# USB.net
KiCad netlist of a schematic drawn in Altium Designer
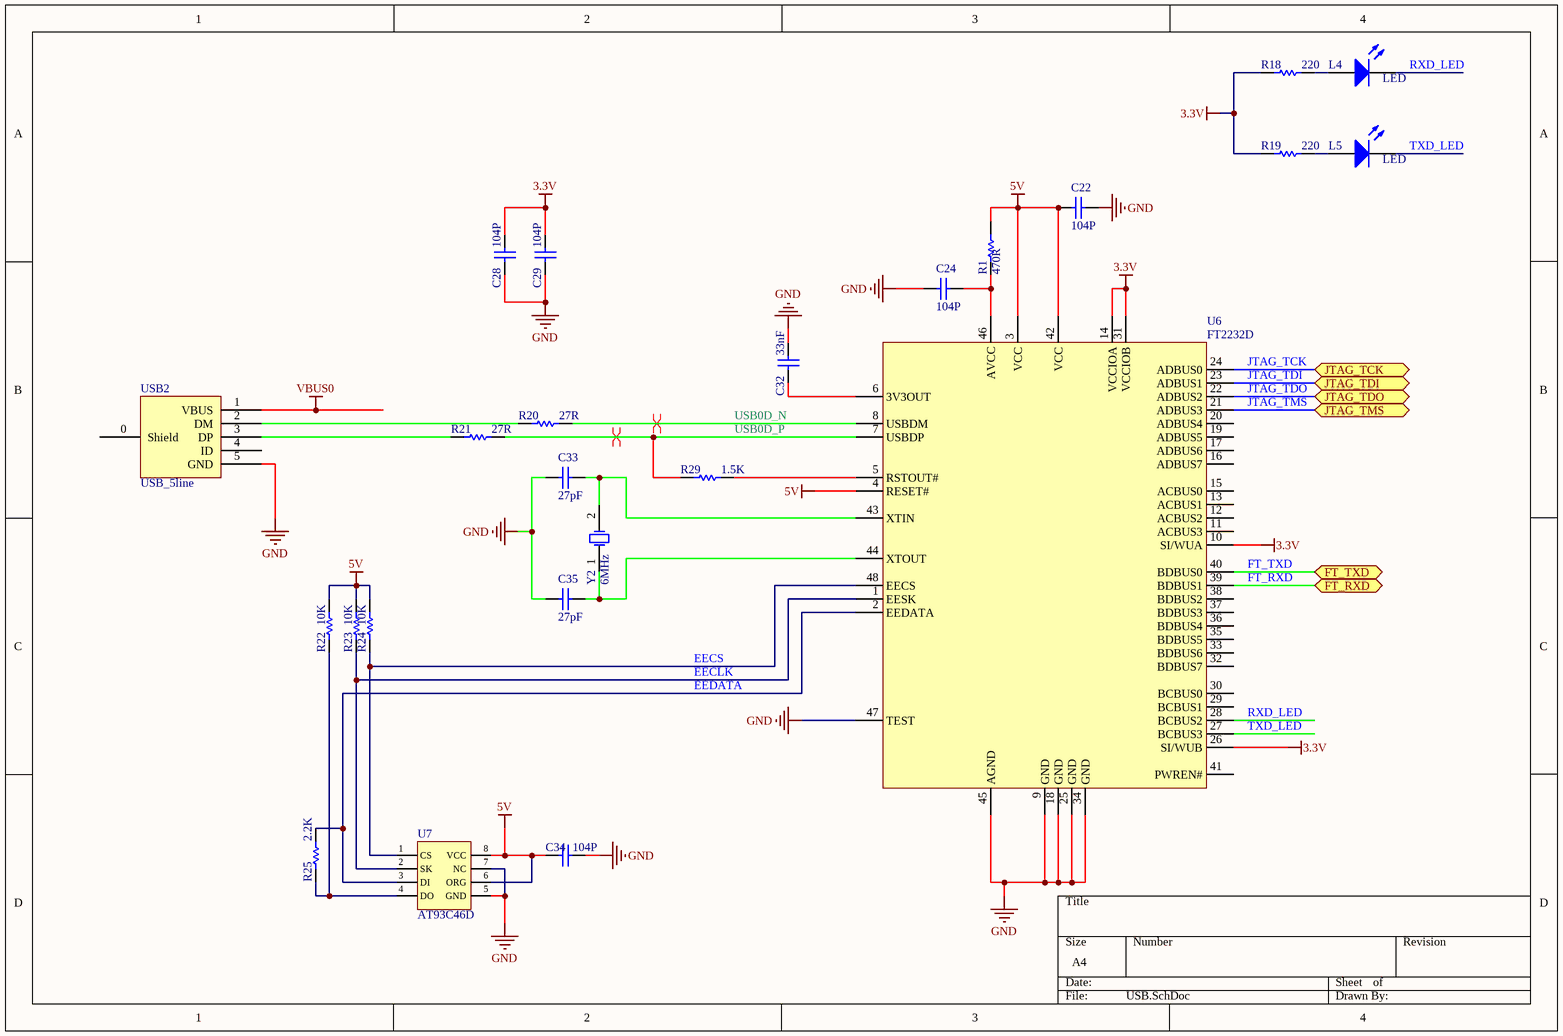
[diagram p0: USB.SchDoc]

(export (version "E")
  (design (tool "Eeschema 10.0.6"))
  (components
    (comp (ref "C22")
      (value "104P")
      (footprint "1608[0603]")
      (description "贴片电容")
      (fields (field (name "Comment") "Cap") (field (name "PUBLISHER") "Altium Limited"))
      (libsource (lib "Sparks") (part "Cap"))
    )
    (comp (ref "C24")
      (value "104P")
      (footprint "1608[0603]")
      (description "贴片电容")
      (fields (field (name "Comment") "Cap") (field (name "PUBLISHER") "Altium Limited"))
      (libsource (lib "Sparks") (part "Cap"))
    )
    (comp (ref "C28")
      (value "104P")
      (footprint "1608[0603]")
      (description "贴片电容")
      (fields (field (name "Comment") "Cap") (field (name "PUBLISHER") "Altium Limited"))
      (libsource (lib "Sparks") (part "Cap"))
    )
    (comp (ref "C29")
      (value "104P")
      (footprint "1608[0603]")
      (description "贴片电容")
      (fields (field (name "Comment") "Cap") (field (name "PUBLISHER") "Altium Limited"))
      (libsource (lib "Sparks") (part "Cap"))
    )
    (comp (ref "C32")
      (value "33nF")
      (footprint "1608[0603]")
      (description "贴片电容")
      (fields (field (name "Comment") "Cap") (field (name "PUBLISHER") "Altium Limited"))
      (libsource (lib "Sparks") (part "Cap"))
    )
    (comp (ref "C33")
      (value "27pF")
      (footprint "1608[0603]")
      (description "贴片电容")
      (fields (field (name "Comment") "Cap") (field (name "PUBLISHER") "Altium Limited"))
      (libsource (lib "Sparks") (part "Cap"))
    )
    (comp (ref "C34")
      (value "104P")
      (footprint "1608[0603]")
      (description "贴片电容")
      (fields (field (name "Comment") "Cap") (field (name "PUBLISHER") "Altium Limited"))
      (libsource (lib "Sparks") (part "Cap"))
    )
    (comp (ref "C35")
      (value "27pF")
      (footprint "1608[0603]")
      (description "贴片电容")
      (fields (field (name "Comment") "Cap") (field (name "PUBLISHER") "Altium Limited"))
      (libsource (lib "Sparks") (part "Cap"))
    )
    (comp (ref "L4") (value "LED") (footprint "1608[0603]") (libsource (lib "Sparks") (part "LED")))
    (comp (ref "L5") (value "LED") (footprint "1608[0603]") (libsource (lib "Sparks") (part "LED")))
    (comp (ref "R1")
      (value "470R")
      (footprint "1608[0603]")
      (description "贴片电阻")
      (fields (field (name "Comment") "Res") (field (name "PUBLISHER") "Altium Limited"))
      (libsource (lib "Sparks") (part "Res"))
    )
    (comp (ref "R18")
      (value "220")
      (footprint "1608[0603]")
      (description "贴片电阻")
      (fields (field (name "Comment") "Res") (field (name "PUBLISHER") "Altium Limited"))
      (libsource (lib "Sparks") (part "Res"))
    )
    (comp (ref "R19")
      (value "220")
      (footprint "1608[0603]")
      (description "贴片电阻")
      (fields (field (name "Comment") "Res") (field (name "PUBLISHER") "Altium Limited"))
      (libsource (lib "Sparks") (part "Res"))
    )
    (comp (ref "R20")
      (value "27R")
      (footprint "R2012")
      (description "贴片电阻")
      (fields (field (name "Comment") "Res") (field (name "PUBLISHER") "Altium Limited"))
      (libsource (lib "Sparks") (part "Res"))
    )
    (comp (ref "R21")
      (value "27R")
      (footprint "R2012")
      (description "贴片电阻")
      (fields (field (name "Comment") "Res") (field (name "PUBLISHER") "Altium Limited"))
      (libsource (lib "Sparks") (part "Res"))
    )
    (comp (ref "R22")
      (value "10K")
      (footprint "1608[0603]")
      (description "贴片电阻")
      (fields (field (name "Comment") "Res") (field (name "PUBLISHER") "Altium Limited"))
      (libsource (lib "Sparks") (part "Res"))
    )
    (comp (ref "R23")
      (value "10K")
      (footprint "1608[0603]")
      (description "贴片电阻")
      (fields (field (name "Comment") "Res") (field (name "PUBLISHER") "Altium Limited"))
      (libsource (lib "Sparks") (part "Res"))
    )
    (comp (ref "R24")
      (value "10K")
      (footprint "1608[0603]")
      (description "贴片电阻")
      (fields (field (name "Comment") "Res") (field (name "PUBLISHER") "Altium Limited"))
      (libsource (lib "Sparks") (part "Res"))
    )
    (comp (ref "R25")
      (value "2.2K")
      (footprint "1608[0603]")
      (description "贴片电阻")
      (fields (field (name "Comment") "Res") (field (name "PUBLISHER") "Altium Limited"))
      (libsource (lib "Sparks") (part "Res"))
    )
    (comp (ref "R29")
      (value "1.5K")
      (footprint "1608[0603]")
      (description "贴片电阻")
      (fields (field (name "Comment") "Res") (field (name "PUBLISHER") "Altium Limited"))
      (libsource (lib "Sparks") (part "Res"))
    )
    (comp (ref "U6")
      (value "FT2232D")
      (footprint "TSQFP50P900X900X160-48N")
      (libsource (lib "2号库") (part "FT2232D"))
    )
    (comp (ref "U7")
      (value "AT93C46D")
      (footprint "TSOP65P640X120-8N-AT93C46D")
      (libsource (lib "2号库") (part "AT93C46D"))
    )
    (comp (ref "USB2")
      (value "USB_5line")
      (footprint "USB-MICRO-5P-2F")
      (libsource (lib "2号库") (part "USB_5line"))
    )
    (comp (ref "Y2")
      (value "6MHz")
      (footprint "5032")
      (description "晶体振荡器")
      (fields (field (name "PUBLISHER") "Altium Limited"))
      (libsource (lib "Sparks") (part "XTAL"))
    )
  )
  (nets
    (net (code "1") (name "/EECLK") (class "Default")
      (node (ref "R23") (pin "2") (pinfunction "2_2") (pintype "passive"))
      (node (ref "U6") (pin "1") (pinfunction "EESK_1") (pintype "passive"))
      (node (ref "U7") (pin "2") (pinfunction "SK_2") (pintype "passive"))
    )
    (net (code "2") (name "/EECS") (class "Default")
      (node (ref "R24") (pin "2") (pinfunction "2_2") (pintype "passive"))
      (node (ref "U6") (pin "48") (pinfunction "EECS_48") (pintype "passive"))
      (node (ref "U7") (pin "1") (pinfunction "CS_1") (pintype "passive"))
    )
    (net (code "3") (name "/EEDATA") (class "Default")
      (node (ref "R25") (pin "1") (pinfunction "1_1") (pintype "passive"))
      (node (ref "U6") (pin "2") (pinfunction "EEDATA_2") (pintype "passive"))
      (node (ref "U7") (pin "3") (pinfunction "DI_3") (pintype "passive"))
    )
    (net (code "4") (name "/FT_RXD") (class "Default")
      (node (ref "U6") (pin "39") (pinfunction "BDBUS1_39") (pintype "passive"))
    )
    (net (code "5") (name "/FT_TXD") (class "Default")
      (node (ref "U6") (pin "40") (pinfunction "BDBUS0_40") (pintype "passive"))
    )
    (net (code "6") (name "/JTAG_TCK") (class "Default")
      (node (ref "U6") (pin "24") (pinfunction "ADBUS0_24") (pintype "passive"))
    )
    (net (code "7") (name "/JTAG_TDI") (class "Default")
      (node (ref "U6") (pin "23") (pinfunction "ADBUS1_23") (pintype "passive"))
    )
    (net (code "8") (name "/JTAG_TDO") (class "Default")
      (node (ref "U6") (pin "22") (pinfunction "ADBUS2_22") (pintype "passive"))
    )
    (net (code "9") (name "/JTAG_TMS") (class "Default")
      (node (ref "U6") (pin "21") (pinfunction "ADBUS3_21") (pintype "passive"))
    )
    (net (code "10") (name "/RXD_LED") (class "Default")
      (node (ref "L4") (pin "2") (pinfunction "K_2") (pintype "passive"))
      (node (ref "U6") (pin "28") (pinfunction "BCBUS2_28") (pintype "passive"))
    )
    (net (code "11") (name "/TXD_LED") (class "Default")
      (node (ref "L5") (pin "2") (pinfunction "K_2") (pintype "passive"))
      (node (ref "U6") (pin "27") (pinfunction "BCBUS3_27") (pintype "passive"))
    )
    (net (code "12") (name "/USB0D_N") (class "Default")
      (node (ref "R20") (pin "2") (pinfunction "2_2") (pintype "passive"))
      (node (ref "U6") (pin "8") (pinfunction "USBDM_8") (pintype "passive"))
    )
    (net (code "13") (name "/USB0D_P") (class "Default")
      (node (ref "R21") (pin "2") (pinfunction "2_2") (pintype "passive"))
      (node (ref "R29") (pin "1") (pinfunction "1_1") (pintype "passive"))
      (node (ref "U6") (pin "7") (pinfunction "USBDP_7") (pintype "passive"))
    )
    (net (code "14") (name "3.3V") (class "Default")
      (node (ref "C28") (pin "2") (pinfunction "2_2") (pintype "passive"))
      (node (ref "C29") (pin "2") (pinfunction "2_2") (pintype "passive"))
      (node (ref "R18") (pin "2") (pinfunction "2_2") (pintype "passive"))
      (node (ref "R19") (pin "2") (pinfunction "2_2") (pintype "passive"))
      (node (ref "U6") (pin "10") (pinfunction "SI/WUA_10") (pintype "passive"))
      (node (ref "U6") (pin "14") (pinfunction "VCCIOA_14") (pintype "passive"))
      (node (ref "U6") (pin "26") (pinfunction "SI/WUB_26") (pintype "passive"))
      (node (ref "U6") (pin "31") (pinfunction "VCCIOB_31") (pintype "passive"))
    )
    (net (code "15") (name "5V") (class "Default")
      (node (ref "C22") (pin "2") (pinfunction "2_2") (pintype "passive"))
      (node (ref "C34") (pin "2") (pinfunction "2_2") (pintype "passive"))
      (node (ref "R1") (pin "1") (pinfunction "1_1") (pintype "passive"))
      (node (ref "R22") (pin "1") (pinfunction "1_1") (pintype "passive"))
      (node (ref "R23") (pin "1") (pinfunction "1_1") (pintype "passive"))
      (node (ref "R24") (pin "1") (pinfunction "1_1") (pintype "passive"))
      (node (ref "U6") (pin "3") (pinfunction "VCC_3") (pintype "passive"))
      (node (ref "U6") (pin "4") (pinfunction "RESET#_4") (pintype "passive"))
      (node (ref "U6") (pin "42") (pinfunction "VCC_42") (pintype "passive"))
      (node (ref "U7") (pin "6") (pinfunction "ORG_6") (pintype "passive"))
      (node (ref "U7") (pin "8") (pinfunction "VCC_8") (pintype "passive"))
    )
    (net (code "16") (name "GND") (class "Default")
      (node (ref "C22") (pin "1") (pinfunction "1_1") (pintype "passive"))
      (node (ref "C24") (pin "2") (pinfunction "2_2") (pintype "passive"))
      (node (ref "C28") (pin "1") (pinfunction "1_1") (pintype "passive"))
      (node (ref "C29") (pin "1") (pinfunction "1_1") (pintype "passive"))
      (node (ref "C32") (pin "2") (pinfunction "2_2") (pintype "passive"))
      (node (ref "C33") (pin "1") (pinfunction "1_1") (pintype "passive"))
      (node (ref "C34") (pin "1") (pinfunction "1_1") (pintype "passive"))
      (node (ref "C35") (pin "2") (pinfunction "2_2") (pintype "passive"))
      (node (ref "U6") (pin "18") (pinfunction "GND_18") (pintype "passive"))
      (node (ref "U6") (pin "25") (pinfunction "GND_25") (pintype "passive"))
      (node (ref "U6") (pin "34") (pinfunction "GND_34") (pintype "passive"))
      (node (ref "U6") (pin "45") (pinfunction "AGND_45") (pintype "passive"))
      (node (ref "U6") (pin "47") (pinfunction "TEST_47") (pintype "passive"))
      (node (ref "U6") (pin "9") (pinfunction "GND_9") (pintype "passive"))
      (node (ref "U7") (pin "5") (pinfunction "GND_5") (pintype "passive"))
      (node (ref "U7") (pin "7") (pinfunction "NC_7") (pintype "passive"))
      (node (ref "USB2") (pin "5") (pinfunction "GND_5") (pintype "passive"))
    )
    (net (code "17") (name "Net-(L4-A)") (class "Default")
      (node (ref "L4") (pin "1") (pinfunction "A_1") (pintype "passive"))
      (node (ref "R18") (pin "1") (pinfunction "1_1") (pintype "passive"))
    )
    (net (code "18") (name "Net-(L5-A)") (class "Default")
      (node (ref "L5") (pin "1") (pinfunction "A_1") (pintype "passive"))
      (node (ref "R19") (pin "1") (pinfunction "1_1") (pintype "passive"))
    )
    (net (code "19") (name "Net-(U6-3V3OUT)") (class "Default")
      (node (ref "C32") (pin "1") (pinfunction "1_1") (pintype "passive"))
      (node (ref "U6") (pin "6") (pinfunction "3V3OUT_6") (pintype "passive"))
    )
    (net (code "20") (name "Net-(U6-AVCC)") (class "Default")
      (node (ref "C24") (pin "1") (pinfunction "1_1") (pintype "passive"))
      (node (ref "R1") (pin "2") (pinfunction "2_2") (pintype "passive"))
      (node (ref "U6") (pin "46") (pinfunction "AVCC_46") (pintype "passive"))
    )
    (net (code "21") (name "Net-(U6-RSTOUT#)") (class "Default")
      (node (ref "R29") (pin "2") (pinfunction "2_2") (pintype "passive"))
      (node (ref "U6") (pin "5") (pinfunction "RSTOUT#_5") (pintype "passive"))
    )
    (net (code "22") (name "Net-(U6-XTIN)") (class "Default")
      (node (ref "C33") (pin "2") (pinfunction "2_2") (pintype "passive"))
      (node (ref "U6") (pin "43") (pinfunction "XTIN_43") (pintype "passive"))
      (node (ref "Y2") (pin "2") (pinfunction "OSC2_2") (pintype "passive"))
    )
    (net (code "23") (name "Net-(U6-XTOUT)") (class "Default")
      (node (ref "C35") (pin "1") (pinfunction "1_1") (pintype "passive"))
      (node (ref "U6") (pin "44") (pinfunction "XTOUT_44") (pintype "passive"))
      (node (ref "Y2") (pin "1") (pinfunction "OSC1_1") (pintype "passive"))
    )
    (net (code "24") (name "Net-(U7-DO)") (class "Default")
      (node (ref "R22") (pin "2") (pinfunction "2_2") (pintype "passive"))
      (node (ref "R25") (pin "2") (pinfunction "2_2") (pintype "passive"))
      (node (ref "U7") (pin "4") (pinfunction "DO_4") (pintype "passive"))
    )
    (net (code "25") (name "Net-(USB2-DM)") (class "Default")
      (node (ref "R20") (pin "1") (pinfunction "1_1") (pintype "passive"))
      (node (ref "USB2") (pin "2") (pinfunction "DM_2") (pintype "passive"))
    )
    (net (code "26") (name "Net-(USB2-DP)") (class "Default")
      (node (ref "R21") (pin "1") (pinfunction "1_1") (pintype "passive"))
      (node (ref "USB2") (pin "3") (pinfunction "DP_3") (pintype "passive"))
    )
    (net (code "27") (name "VBUS0") (class "Default")
      (node (ref "USB2") (pin "1") (pinfunction "VBUS_1") (pintype "passive"))
    )
    (net (code "28") (name "unconnected-(U6-ACBUS0-Pad15)") (class "Default")
      (node (ref "U6") (pin "15") (pinfunction "ACBUS0_15") (pintype "passive"))
    )
    (net (code "29") (name "unconnected-(U6-ACBUS1-Pad13)") (class "Default")
      (node (ref "U6") (pin "13") (pinfunction "ACBUS1_13") (pintype "passive"))
    )
    (net (code "30") (name "unconnected-(U6-ACBUS2-Pad12)") (class "Default")
      (node (ref "U6") (pin "12") (pinfunction "ACBUS2_12") (pintype "passive"))
    )
    (net (code "31") (name "unconnected-(U6-ACBUS3-Pad11)") (class "Default")
      (node (ref "U6") (pin "11") (pinfunction "ACBUS3_11") (pintype "passive"))
    )
    (net (code "32") (name "unconnected-(U6-ADBUS4-Pad20)") (class "Default")
      (node (ref "U6") (pin "20") (pinfunction "ADBUS4_20") (pintype "passive"))
    )
    (net (code "33") (name "unconnected-(U6-ADBUS5-Pad19)") (class "Default")
      (node (ref "U6") (pin "19") (pinfunction "ADBUS5_19") (pintype "passive"))
    )
    (net (code "34") (name "unconnected-(U6-ADBUS6-Pad17)") (class "Default")
      (node (ref "U6") (pin "17") (pinfunction "ADBUS6_17") (pintype "passive"))
    )
    (net (code "35") (name "unconnected-(U6-ADBUS7-Pad16)") (class "Default")
      (node (ref "U6") (pin "16") (pinfunction "ADBUS7_16") (pintype "passive"))
    )
    (net (code "36") (name "unconnected-(U6-BCBUS0-Pad30)") (class "Default")
      (node (ref "U6") (pin "30") (pinfunction "BCBUS0_30") (pintype "passive"))
    )
    (net (code "37") (name "unconnected-(U6-BCBUS1-Pad29)") (class "Default")
      (node (ref "U6") (pin "29") (pinfunction "BCBUS1_29") (pintype "passive"))
    )
    (net (code "38") (name "unconnected-(U6-BDBUS2-Pad38)") (class "Default")
      (node (ref "U6") (pin "38") (pinfunction "BDBUS2_38") (pintype "passive"))
    )
    (net (code "39") (name "unconnected-(U6-BDBUS3-Pad37)") (class "Default")
      (node (ref "U6") (pin "37") (pinfunction "BDBUS3_37") (pintype "passive"))
    )
    (net (code "40") (name "unconnected-(U6-BDBUS4-Pad36)") (class "Default")
      (node (ref "U6") (pin "36") (pinfunction "BDBUS4_36") (pintype "passive"))
    )
    (net (code "41") (name "unconnected-(U6-BDBUS5-Pad35)") (class "Default")
      (node (ref "U6") (pin "35") (pinfunction "BDBUS5_35") (pintype "passive"))
    )
    (net (code "42") (name "unconnected-(U6-BDBUS6-Pad33)") (class "Default")
      (node (ref "U6") (pin "33") (pinfunction "BDBUS6_33") (pintype "passive"))
    )
    (net (code "43") (name "unconnected-(U6-BDBUS7-Pad32)") (class "Default")
      (node (ref "U6") (pin "32") (pinfunction "BDBUS7_32") (pintype "passive"))
    )
    (net (code "44") (name "unconnected-(U6-PWREN#-Pad41)") (class "Default")
      (node (ref "U6") (pin "41") (pinfunction "PWREN#_41") (pintype "passive"))
    )
    (net (code "45") (name "unconnected-(USB2-ID-Pad4)") (class "Default")
      (node (ref "USB2") (pin "4") (pinfunction "ID_4") (pintype "passive"))
    )
    (net (code "46") (name "unconnected-(USB2-Shield-Pad0)") (class "Default")
      (node (ref "USB2") (pin "0") (pinfunction "Shield_0") (pintype "passive"))
    )
  )
)
